# S7CAS-PLEIADES-CARTE-MERE_P01_CLOCK.net
KiCad netlist of a schematic drawn in Altium Designer
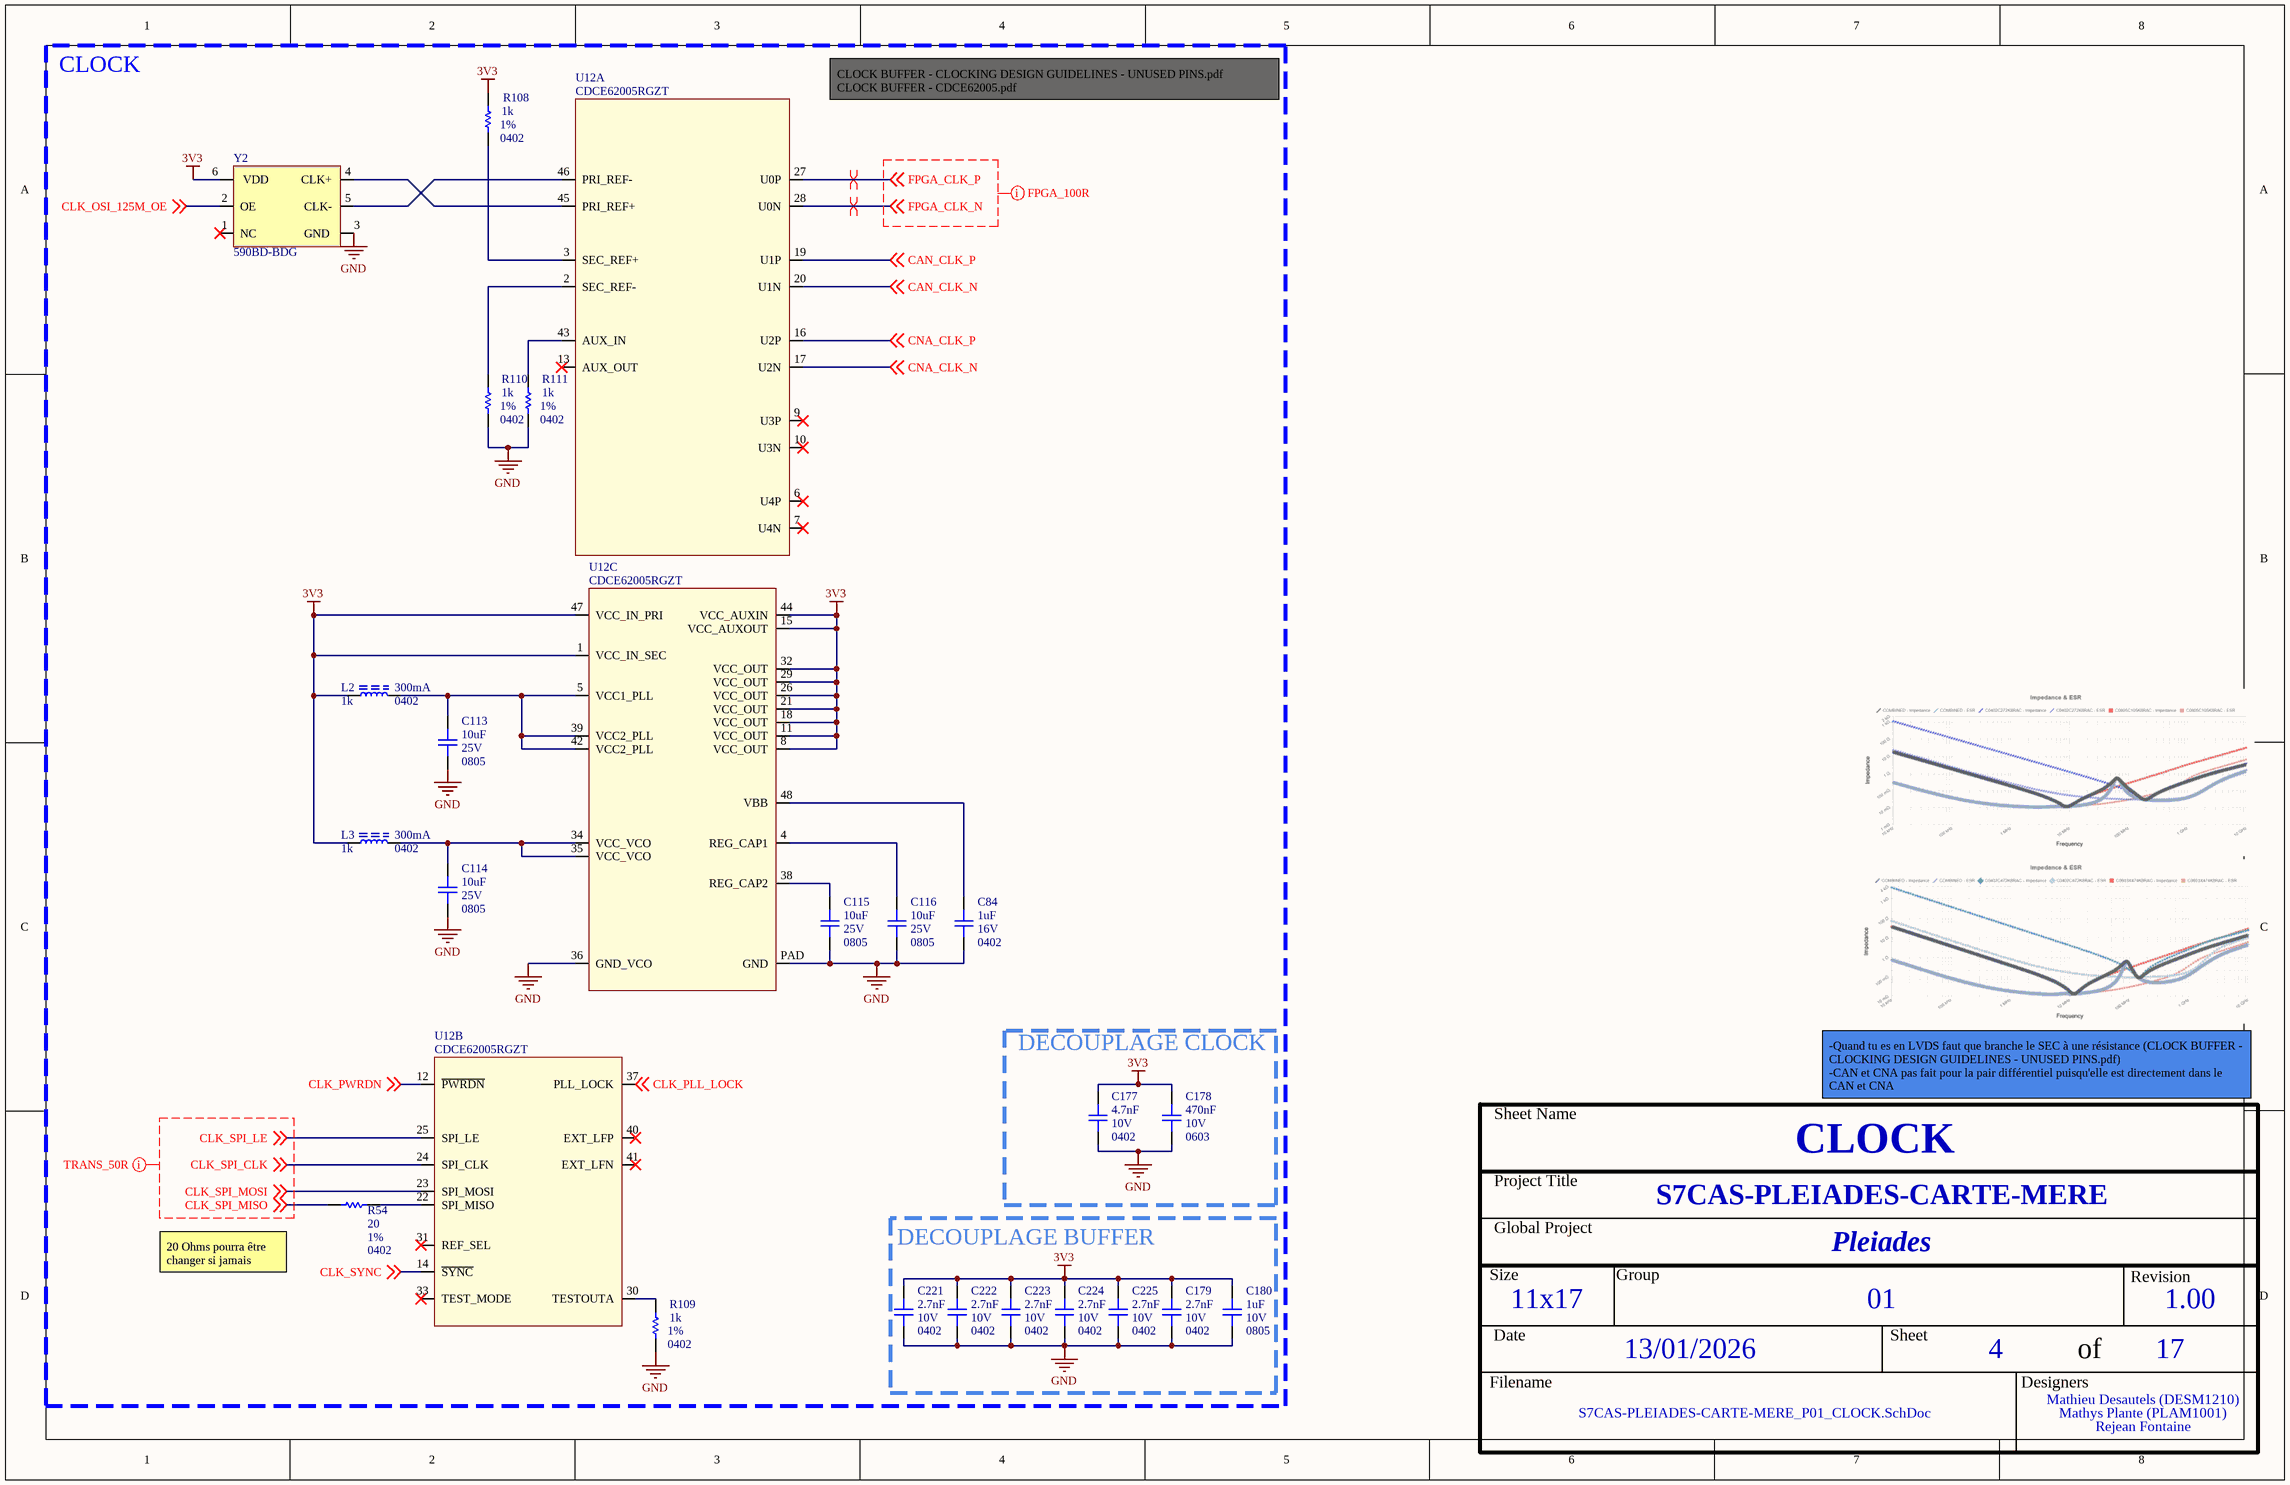
[diagram p0: S7CAS-PLEIADES-CARTE-MERE_P01_CLOCK.SchDoc]

(export (version "E")
  (design (tool "Eeschema 10.0.6"))
  (components
    (comp (ref "C84")
      (value "1uF")
      (footprint "CAP_0402")
      (description "1 µF ±10% 16V Ceramic Capacitor X5R 0402 (1005 Metric)")
      (fields
        (field (name "MFG") "Samsung Electro-Mechanics")
        (field (name "MFG PART NUMBER") "CL05A105KO5NNNC")
        (field (name "VOLTAGE") "16V")
        (field (name "PACKAGE") "0402")
        (field (name "CREATEDBY") "Jonathan Bouchard")
      )
      (libsource (lib "s7cas_lib2023") (part "CAP - 0402"))
    )
    (comp (ref "C113")
      (value "10uF")
      (footprint "CAP_0805")
      (description "10 µF ±10% 25V Ceramic Capacitor X5R 0805 (2012 Metric)")
      (fields
        (field (name "MFG") "Samsung Electro-Mechanics")
        (field (name "MFG PART NUMBER") "CL21A106KAYNNNE")
        (field (name "VOLTAGE") "25V")
        (field (name "PACKAGE") "0805")
        (field (name "CREATEDBY") "Jonathan Bouchard")
      )
      (libsource (lib "s7cas_lib2023") (part "CAP - 0805"))
    )
    (comp (ref "C114")
      (value "10uF")
      (footprint "CAP_0805")
      (description "10 µF ±10% 25V Ceramic Capacitor X5R 0805 (2012 Metric)")
      (fields
        (field (name "MFG") "Samsung Electro-Mechanics")
        (field (name "MFG PART NUMBER") "CL21A106KAYNNNE")
        (field (name "VOLTAGE") "25V")
        (field (name "PACKAGE") "0805")
        (field (name "CREATEDBY") "Jonathan Bouchard")
      )
      (libsource (lib "s7cas_lib2023") (part "CAP - 0805"))
    )
    (comp (ref "C115")
      (value "10uF")
      (footprint "CAP_0805")
      (description "10 µF ±10% 25V Ceramic Capacitor X5R 0805 (2012 Metric)")
      (fields
        (field (name "MFG") "Samsung Electro-Mechanics")
        (field (name "MFG PART NUMBER") "CL21A106KAYNNNE")
        (field (name "VOLTAGE") "25V")
        (field (name "PACKAGE") "0805")
        (field (name "CREATEDBY") "Jonathan Bouchard")
      )
      (libsource (lib "s7cas_lib2023") (part "CAP - 0805"))
    )
    (comp (ref "C116")
      (value "10uF")
      (footprint "CAP_0805")
      (description "10 µF ±10% 25V Ceramic Capacitor X5R 0805 (2012 Metric)")
      (fields
        (field (name "MFG") "Samsung Electro-Mechanics")
        (field (name "MFG PART NUMBER") "CL21A106KAYNNNE")
        (field (name "VOLTAGE") "25V")
        (field (name "PACKAGE") "0805")
        (field (name "CREATEDBY") "Jonathan Bouchard")
      )
      (libsource (lib "s7cas_lib2023") (part "CAP - 0805"))
    )
    (comp (ref "C177")
      (value "4.7nF")
      (footprint "CAP_0402")
      (description "CAP - 0402")
      (fields
        (field (name "MFG PART NUMBER") "C0402C472K8RAC")
        (field (name "VOLTAGE") "10V")
        (field (name "PACKAGE") "0402")
        (field (name "CREATEDBY") "Jonathan Bouchard")
      )
      (libsource (lib "s7cas_lib2023") (part "CAP - 0402"))
    )
    (comp (ref "C178")
      (value "470nF")
      (footprint "CAP_0603")
      (description "CAP - 0603")
      (fields
        (field (name "MFG PART NUMBER") "C0603X474K8RAC")
        (field (name "VOLTAGE") "10V")
        (field (name "PACKAGE") "0603")
        (field (name "CREATEDBY") "Jonathan Bouchard")
      )
      (libsource (lib "s7cas_lib2023") (part "CAP - 0603"))
    )
    (comp (ref "C179")
      (value "2.7nF")
      (footprint "CAP_0402")
      (description "CAP - 0402")
      (fields
        (field (name "MFG PART NUMBER") "C0402C272K8RAC")
        (field (name "VOLTAGE") "10V")
        (field (name "PACKAGE") "0402")
        (field (name "CREATEDBY") "Jonathan Bouchard")
      )
      (libsource (lib "s7cas_lib2023") (part "CAP - 0402"))
    )
    (comp (ref "C180")
      (value "1uF")
      (footprint "CAP_0805")
      (description "CAP - 0805")
      (fields
        (field (name "MFG PART NUMBER") "C0805C105K8RAC")
        (field (name "VOLTAGE") "10V")
        (field (name "PACKAGE") "0805")
        (field (name "CREATEDBY") "Jonathan Bouchard")
      )
      (libsource (lib "s7cas_lib2023") (part "CAP - 0805"))
    )
    (comp (ref "C221")
      (value "2.7nF")
      (footprint "CAP_0402")
      (description "CAP - 0402")
      (fields
        (field (name "MFG PART NUMBER") "C0402C272K8RAC")
        (field (name "VOLTAGE") "10V")
        (field (name "PACKAGE") "0402")
        (field (name "CREATEDBY") "Jonathan Bouchard")
      )
      (libsource (lib "s7cas_lib2023") (part "CAP - 0402"))
    )
    (comp (ref "C222")
      (value "2.7nF")
      (footprint "CAP_0402")
      (description "CAP - 0402")
      (fields
        (field (name "MFG PART NUMBER") "C0402C272K8RAC")
        (field (name "VOLTAGE") "10V")
        (field (name "PACKAGE") "0402")
        (field (name "CREATEDBY") "Jonathan Bouchard")
      )
      (libsource (lib "s7cas_lib2023") (part "CAP - 0402"))
    )
    (comp (ref "C223")
      (value "2.7nF")
      (footprint "CAP_0402")
      (description "CAP - 0402")
      (fields
        (field (name "MFG PART NUMBER") "C0402C272K8RAC")
        (field (name "VOLTAGE") "10V")
        (field (name "PACKAGE") "0402")
        (field (name "CREATEDBY") "Jonathan Bouchard")
      )
      (libsource (lib "s7cas_lib2023") (part "CAP - 0402"))
    )
    (comp (ref "C224")
      (value "2.7nF")
      (footprint "CAP_0402")
      (description "CAP - 0402")
      (fields
        (field (name "MFG PART NUMBER") "C0402C272K8RAC")
        (field (name "VOLTAGE") "10V")
        (field (name "PACKAGE") "0402")
        (field (name "CREATEDBY") "Jonathan Bouchard")
      )
      (libsource (lib "s7cas_lib2023") (part "CAP - 0402"))
    )
    (comp (ref "C225")
      (value "2.7nF")
      (footprint "CAP_0402")
      (description "CAP - 0402")
      (fields
        (field (name "MFG PART NUMBER") "C0402C272K8RAC")
        (field (name "VOLTAGE") "10V")
        (field (name "PACKAGE") "0402")
        (field (name "CREATEDBY") "Jonathan Bouchard")
      )
      (libsource (lib "s7cas_lib2023") (part "CAP - 0402"))
    )
    (comp (ref "L2")
      (value "1k")
      (footprint "FER_0402")
      (description "1 kOhms @ 100 MHz 1 Ferrite Bead 0402 (1005 Metric) 300mA 650mOhm")
      (fields
        (field (name "MFG") "Murata Electronics")
        (field (name "MFG PART NUMBER") "BLM15AG102SN1D")
        (field (name "CURRENT") "300mA")
        (field (name "PACKAGE") "0402")
        (field (name "CREATEDBY") "Jonathan Bouchard")
      )
      (libsource (lib "s7cas_lib2023") (part "FER - 0402"))
    )
    (comp (ref "L3")
      (value "1k")
      (footprint "FER_0402")
      (description "1 kOhms @ 100 MHz 1 Ferrite Bead 0402 (1005 Metric) 300mA 650mOhm")
      (fields
        (field (name "MFG") "Murata Electronics")
        (field (name "MFG PART NUMBER") "BLM15AG102SN1D")
        (field (name "CURRENT") "300mA")
        (field (name "PACKAGE") "0402")
        (field (name "CREATEDBY") "Jonathan Bouchard")
      )
      (libsource (lib "s7cas_lib2023") (part "FER - 0402"))
    )
    (comp (ref "R54")
      (value "20")
      (footprint "RES_0402")
      (description "20 Ohms ±1% 0.063W, 1/16W Chip Resistor 0402 (1005 Metric) Moisture Resistant Thick Film")
      (fields
        (field (name "VOLTAGE") "75V")
        (field (name "MFG PART NUMBER") "RC0402FR-0720RL")
        (field (name "PACKAGE") "0402")
        (field (name "PRECISION") "1%")
        (field (name "CREATEDBY") "Jonathan Bouchard")
      )
      (libsource (lib "s7cas_lib2023") (part "RES - 0402"))
    )
    (comp (ref "R108")
      (value "1k")
      (footprint "RES_0402")
      (description "1 kOhms ±1% 0.1W, 1/10W Chip Resistor 0402 (1005 Metric) Automotive AEC-Q200 Thick Film")
      (fields
        (field (name "VOLTAGE") "50V")
        (field (name "MFG") "Panasonic Electronic Components")
        (field (name "PACKAGE") "0402")
        (field (name "PRECISION") "1%")
        (field (name "CREATEDBY") "Jonathan Bouchard")
      )
      (libsource (lib "s7cas_lib2023") (part "RES - 0402"))
    )
    (comp (ref "R109")
      (value "1k")
      (footprint "RES_0402")
      (description "1 kOhms ±1% 0.1W, 1/10W Chip Resistor 0402 (1005 Metric) Automotive AEC-Q200 Thick Film")
      (fields
        (field (name "VOLTAGE") "50V")
        (field (name "MFG") "Panasonic Electronic Components")
        (field (name "PACKAGE") "0402")
        (field (name "PRECISION") "1%")
        (field (name "CREATEDBY") "Jonathan Bouchard")
      )
      (libsource (lib "s7cas_lib2023") (part "RES - 0402"))
    )
    (comp (ref "R110")
      (value "1k")
      (footprint "RES_0402")
      (description "1 kOhms ±1% 0.1W, 1/10W Chip Resistor 0402 (1005 Metric) Automotive AEC-Q200 Thick Film")
      (fields
        (field (name "VOLTAGE") "50V")
        (field (name "MFG") "Panasonic Electronic Components")
        (field (name "PACKAGE") "0402")
        (field (name "PRECISION") "1%")
        (field (name "CREATEDBY") "Jonathan Bouchard")
      )
      (libsource (lib "s7cas_lib2023") (part "RES - 0402"))
    )
    (comp (ref "R111")
      (value "1k")
      (footprint "RES_0402")
      (description "1 kOhms ±1% 0.1W, 1/10W Chip Resistor 0402 (1005 Metric) Automotive AEC-Q200 Thick Film")
      (fields
        (field (name "VOLTAGE") "50V")
        (field (name "MFG") "Panasonic Electronic Components")
        (field (name "PACKAGE") "0402")
        (field (name "PRECISION") "1%")
        (field (name "CREATEDBY") "Jonathan Bouchard")
      )
      (libsource (lib "s7cas_lib2023") (part "RES - 0402"))
    )
    (comp (ref "U12")
      (value "CDCE62005RGZT")
      (footprint "TIM_CDCE62005RGZT")
      (description "TIM - CLK SYNTH JITTER CLEANER 3:5 - QFN-48")
      (fields
        (field (name "VOLTAGE") "3 V ~ 3.6 V")
        (field (name "MFG") "Texas Instruments")
        (field (name "CREATEDBY") "Jonathan Bouchard")
      )
      (libsource (lib "s7cas_lib2023") (part "TIM_CDCE62005RGZT"))
    )
    (comp (ref "Y2")
      (value "590BD-BDG")
      (footprint "OSC_590BD-BDG")
      (description "TIM - OSC PROG 125MHz ~ 214.999MHz LVDS 3.3V 7PPM EN/DS - 6-SMD")
      (fields
        (field (name "CREATEDBY/DATE") "from 590BD-CDG")
        (field (name "VERIFIEDBY") "Caroline Paulin / 3/10/2019")
      )
      (libsource (lib "s7cas_lib2023") (part "OSC_590BD-BDG"))
    )
  )
  (nets
    (net (code "1") (name "3V3") (class "Default")
      (node (ref "C177") (pin "2") (pinfunction "2_2") (pintype "passive"))
      (node (ref "C178") (pin "2") (pinfunction "2_2") (pintype "passive"))
      (node (ref "C179") (pin "2") (pinfunction "2_2") (pintype "passive"))
      (node (ref "C180") (pin "2") (pinfunction "2_2") (pintype "passive"))
      (node (ref "C221") (pin "2") (pinfunction "2_2") (pintype "passive"))
      (node (ref "C222") (pin "2") (pinfunction "2_2") (pintype "passive"))
      (node (ref "C223") (pin "2") (pinfunction "2_2") (pintype "passive"))
      (node (ref "C224") (pin "2") (pinfunction "2_2") (pintype "passive"))
      (node (ref "C225") (pin "2") (pinfunction "2_2") (pintype "passive"))
      (node (ref "L2") (pin "2") (pinfunction "2_2") (pintype "passive"))
      (node (ref "L3") (pin "2") (pinfunction "2_2") (pintype "passive"))
      (node (ref "R108") (pin "2") (pinfunction "2_2") (pintype "passive"))
      (node (ref "U12") (pin "1") (pinfunction "VCC_IN_SEC_1") (pintype "passive"))
      (node (ref "U12") (pin "11") (pinfunction "VCC_OUT_11") (pintype "passive"))
      (node (ref "U12") (pin "15") (pinfunction "VCC_AUXOUT_15") (pintype "passive"))
      (node (ref "U12") (pin "18") (pinfunction "VCC_OUT_18") (pintype "passive"))
      (node (ref "U12") (pin "21") (pinfunction "VCC_OUT_21") (pintype "passive"))
      (node (ref "U12") (pin "26") (pinfunction "VCC_OUT_26") (pintype "passive"))
      (node (ref "U12") (pin "29") (pinfunction "VCC_OUT_29") (pintype "passive"))
      (node (ref "U12") (pin "32") (pinfunction "VCC_OUT_32") (pintype "passive"))
      (node (ref "U12") (pin "44") (pinfunction "VCC_AUXIN_44") (pintype "passive"))
      (node (ref "U12") (pin "47") (pinfunction "VCC_IN_PRI_47") (pintype "passive"))
      (node (ref "U12") (pin "8") (pinfunction "VCC_OUT_8") (pintype "passive"))
      (node (ref "Y2") (pin "6") (pinfunction "VDD_6") (pintype "passive"))
    )
    (net (code "2") (name "CAN_CLK_N") (class "Default")
      (node (ref "U12") (pin "20") (pinfunction "U1N_20") (pintype "passive"))
    )
    (net (code "3") (name "CAN_CLK_P") (class "Default")
      (node (ref "U12") (pin "19") (pinfunction "U1P_19") (pintype "passive"))
    )
    (net (code "4") (name "CLK_OSI_125M_OE") (class "Default")
      (node (ref "Y2") (pin "2") (pinfunction "OE_2") (pintype "passive"))
    )
    (net (code "5") (name "CLK_PLL_LOCK") (class "Default")
      (node (ref "U12") (pin "37") (pinfunction "PLL_LOCK_37") (pintype "passive"))
    )
    (net (code "6") (name "CLK_PWRDN") (class "Default")
      (node (ref "U12") (pin "12") (pinfunction "~{PWRDN}_12") (pintype "passive"))
    )
    (net (code "7") (name "CLK_SPI_CLK") (class "Default")
      (node (ref "U12") (pin "24") (pinfunction "SPI_CLK_24") (pintype "passive"))
    )
    (net (code "8") (name "CLK_SPI_LE") (class "Default")
      (node (ref "U12") (pin "25") (pinfunction "SPI_LE_25") (pintype "passive"))
    )
    (net (code "9") (name "CLK_SPI_MISO") (class "Default")
      (node (ref "R54") (pin "2") (pinfunction "2_2") (pintype "passive"))
    )
    (net (code "10") (name "CLK_SPI_MOSI") (class "Default")
      (node (ref "U12") (pin "23") (pinfunction "SPI_MOSI_23") (pintype "passive"))
    )
    (net (code "11") (name "CLK_SYNC") (class "Default")
      (node (ref "U12") (pin "14") (pinfunction "~{SYNC}_14") (pintype "passive"))
    )
    (net (code "12") (name "CNA_CLK_N") (class "Default")
      (node (ref "U12") (pin "17") (pinfunction "U2N_17") (pintype "passive"))
    )
    (net (code "13") (name "CNA_CLK_P") (class "Default")
      (node (ref "U12") (pin "16") (pinfunction "U2P_16") (pintype "passive"))
    )
    (net (code "14") (name "FPGA_CLK_N") (class "Default")
      (node (ref "U12") (pin "28") (pinfunction "U0N_28") (pintype "passive"))
    )
    (net (code "15") (name "FPGA_CLK_P") (class "Default")
      (node (ref "U12") (pin "27") (pinfunction "U0P_27") (pintype "passive"))
    )
    (net (code "16") (name "GND") (class "Default")
      (node (ref "C113") (pin "1") (pinfunction "1_1") (pintype "passive"))
      (node (ref "C114") (pin "1") (pinfunction "1_1") (pintype "passive"))
      (node (ref "C115") (pin "1") (pinfunction "1_1") (pintype "passive"))
      (node (ref "C116") (pin "1") (pinfunction "1_1") (pintype "passive"))
      (node (ref "C177") (pin "1") (pinfunction "1_1") (pintype "passive"))
      (node (ref "C178") (pin "1") (pinfunction "1_1") (pintype "passive"))
      (node (ref "C179") (pin "1") (pinfunction "1_1") (pintype "passive"))
      (node (ref "C180") (pin "1") (pinfunction "1_1") (pintype "passive"))
      (node (ref "C221") (pin "1") (pinfunction "1_1") (pintype "passive"))
      (node (ref "C222") (pin "1") (pinfunction "1_1") (pintype "passive"))
      (node (ref "C223") (pin "1") (pinfunction "1_1") (pintype "passive"))
      (node (ref "C224") (pin "1") (pinfunction "1_1") (pintype "passive"))
      (node (ref "C225") (pin "1") (pinfunction "1_1") (pintype "passive"))
      (node (ref "C84") (pin "1") (pinfunction "1_1") (pintype "passive"))
      (node (ref "R109") (pin "1") (pinfunction "1_1") (pintype "passive"))
      (node (ref "R110") (pin "1") (pinfunction "1_1") (pintype "passive"))
      (node (ref "R111") (pin "1") (pinfunction "1_1") (pintype "passive"))
      (node (ref "U12") (pin "36") (pinfunction "GND_VCO_36") (pintype "passive"))
      (node (ref "U12") (pin "PAD") (pinfunction "GND_PAD") (pintype "passive"))
      (node (ref "Y2") (pin "3") (pinfunction "GND_3") (pintype "passive"))
    )
    (net (code "17") (name "Net-(C114-Pad2)") (class "Default")
      (node (ref "C114") (pin "2") (pinfunction "2_2") (pintype "passive"))
      (node (ref "L3") (pin "1") (pinfunction "1_1") (pintype "passive"))
      (node (ref "U12") (pin "34") (pinfunction "VCC_VCO_34") (pintype "passive"))
      (node (ref "U12") (pin "35") (pinfunction "VCC_VCO_35") (pintype "passive"))
    )
    (net (code "18") (name "Net-(U12A-AUX_IN)") (class "Default")
      (node (ref "R111") (pin "2") (pinfunction "2_2") (pintype "passive"))
      (node (ref "U12") (pin "43") (pinfunction "AUX_IN_43") (pintype "passive"))
    )
    (net (code "19") (name "Net-(U12A-PRI_REF+)") (class "Default")
      (node (ref "U12") (pin "45") (pinfunction "PRI_REF+_45") (pintype "passive"))
      (node (ref "Y2") (pin "4") (pinfunction "CLK+_4") (pintype "passive"))
    )
    (net (code "20") (name "Net-(U12A-PRI_REF-)") (class "Default")
      (node (ref "U12") (pin "46") (pinfunction "PRI_REF-_46") (pintype "passive"))
      (node (ref "Y2") (pin "5") (pinfunction "CLK-_5") (pintype "passive"))
    )
    (net (code "21") (name "Net-(U12A-SEC_REF+)") (class "Default")
      (node (ref "R108") (pin "1") (pinfunction "1_1") (pintype "passive"))
      (node (ref "U12") (pin "3") (pinfunction "SEC_REF+_3") (pintype "passive"))
    )
    (net (code "22") (name "Net-(U12A-SEC_REF-)") (class "Default")
      (node (ref "R110") (pin "2") (pinfunction "2_2") (pintype "passive"))
      (node (ref "U12") (pin "2") (pinfunction "SEC_REF-_2") (pintype "passive"))
    )
    (net (code "23") (name "Net-(U12B-SPI_MISO)") (class "Default")
      (node (ref "R54") (pin "1") (pinfunction "1_1") (pintype "passive"))
      (node (ref "U12") (pin "22") (pinfunction "SPI_MISO_22") (pintype "passive"))
    )
    (net (code "24") (name "Net-(U12B-TESTOUTA)") (class "Default")
      (node (ref "R109") (pin "2") (pinfunction "2_2") (pintype "passive"))
      (node (ref "U12") (pin "30") (pinfunction "TESTOUTA_30") (pintype "passive"))
    )
    (net (code "25") (name "Net-(U12C-REG_CAP1)") (class "Default")
      (node (ref "C116") (pin "2") (pinfunction "2_2") (pintype "passive"))
      (node (ref "U12") (pin "4") (pinfunction "REG_CAP1_4") (pintype "passive"))
    )
    (net (code "26") (name "Net-(U12C-REG_CAP2)") (class "Default")
      (node (ref "C115") (pin "2") (pinfunction "2_2") (pintype "passive"))
      (node (ref "U12") (pin "38") (pinfunction "REG_CAP2_38") (pintype "passive"))
    )
    (net (code "27") (name "Net-(U12C-VBB)") (class "Default")
      (node (ref "C84") (pin "2") (pinfunction "2_2") (pintype "passive"))
      (node (ref "U12") (pin "48") (pinfunction "VBB_48") (pintype "passive"))
    )
    (net (code "28") (name "Net-(U12C-VCC1_PLL)") (class "Default")
      (node (ref "C113") (pin "2") (pinfunction "2_2") (pintype "passive"))
      (node (ref "L2") (pin "1") (pinfunction "1_1") (pintype "passive"))
      (node (ref "U12") (pin "39") (pinfunction "VCC2_PLL_39") (pintype "passive"))
      (node (ref "U12") (pin "42") (pinfunction "VCC2_PLL_42") (pintype "passive"))
      (node (ref "U12") (pin "5") (pinfunction "VCC1_PLL_5") (pintype "passive"))
    )
    (net (code "29") (name "unconnected-(U12A-AUX_OUT-Pad13)") (class "Default")
      (node (ref "U12") (pin "13") (pinfunction "AUX_OUT_13") (pintype "passive+no_connect"))
    )
    (net (code "30") (name "unconnected-(U12A-U3N-Pad10)") (class "Default")
      (node (ref "U12") (pin "10") (pinfunction "U3N_10") (pintype "passive+no_connect"))
    )
    (net (code "31") (name "unconnected-(U12A-U3P-Pad9)") (class "Default")
      (node (ref "U12") (pin "9") (pinfunction "U3P_9") (pintype "passive+no_connect"))
    )
    (net (code "32") (name "unconnected-(U12A-U4N-Pad7)") (class "Default")
      (node (ref "U12") (pin "7") (pinfunction "U4N_7") (pintype "passive+no_connect"))
    )
    (net (code "33") (name "unconnected-(U12A-U4P-Pad6)") (class "Default")
      (node (ref "U12") (pin "6") (pinfunction "U4P_6") (pintype "passive+no_connect"))
    )
    (net (code "34") (name "unconnected-(U12B-EXT_LFN-Pad41)") (class "Default")
      (node (ref "U12") (pin "41") (pinfunction "EXT_LFN_41") (pintype "passive+no_connect"))
    )
    (net (code "35") (name "unconnected-(U12B-EXT_LFP-Pad40)") (class "Default")
      (node (ref "U12") (pin "40") (pinfunction "EXT_LFP_40") (pintype "passive+no_connect"))
    )
    (net (code "36") (name "unconnected-(U12B-REF_SEL-Pad31)") (class "Default")
      (node (ref "U12") (pin "31") (pinfunction "REF_SEL_31") (pintype "passive+no_connect"))
    )
    (net (code "37") (name "unconnected-(U12B-TEST_MODE-Pad33)") (class "Default")
      (node (ref "U12") (pin "33") (pinfunction "TEST_MODE_33") (pintype "passive+no_connect"))
    )
    (net (code "38") (name "unconnected-(Y2-NC-Pad1)") (class "Default")
      (node (ref "Y2") (pin "1") (pinfunction "NC_1") (pintype "passive+no_connect"))
    )
  )
)
